# Core.net
KiCad netlist of a schematic drawn in Altium Designer
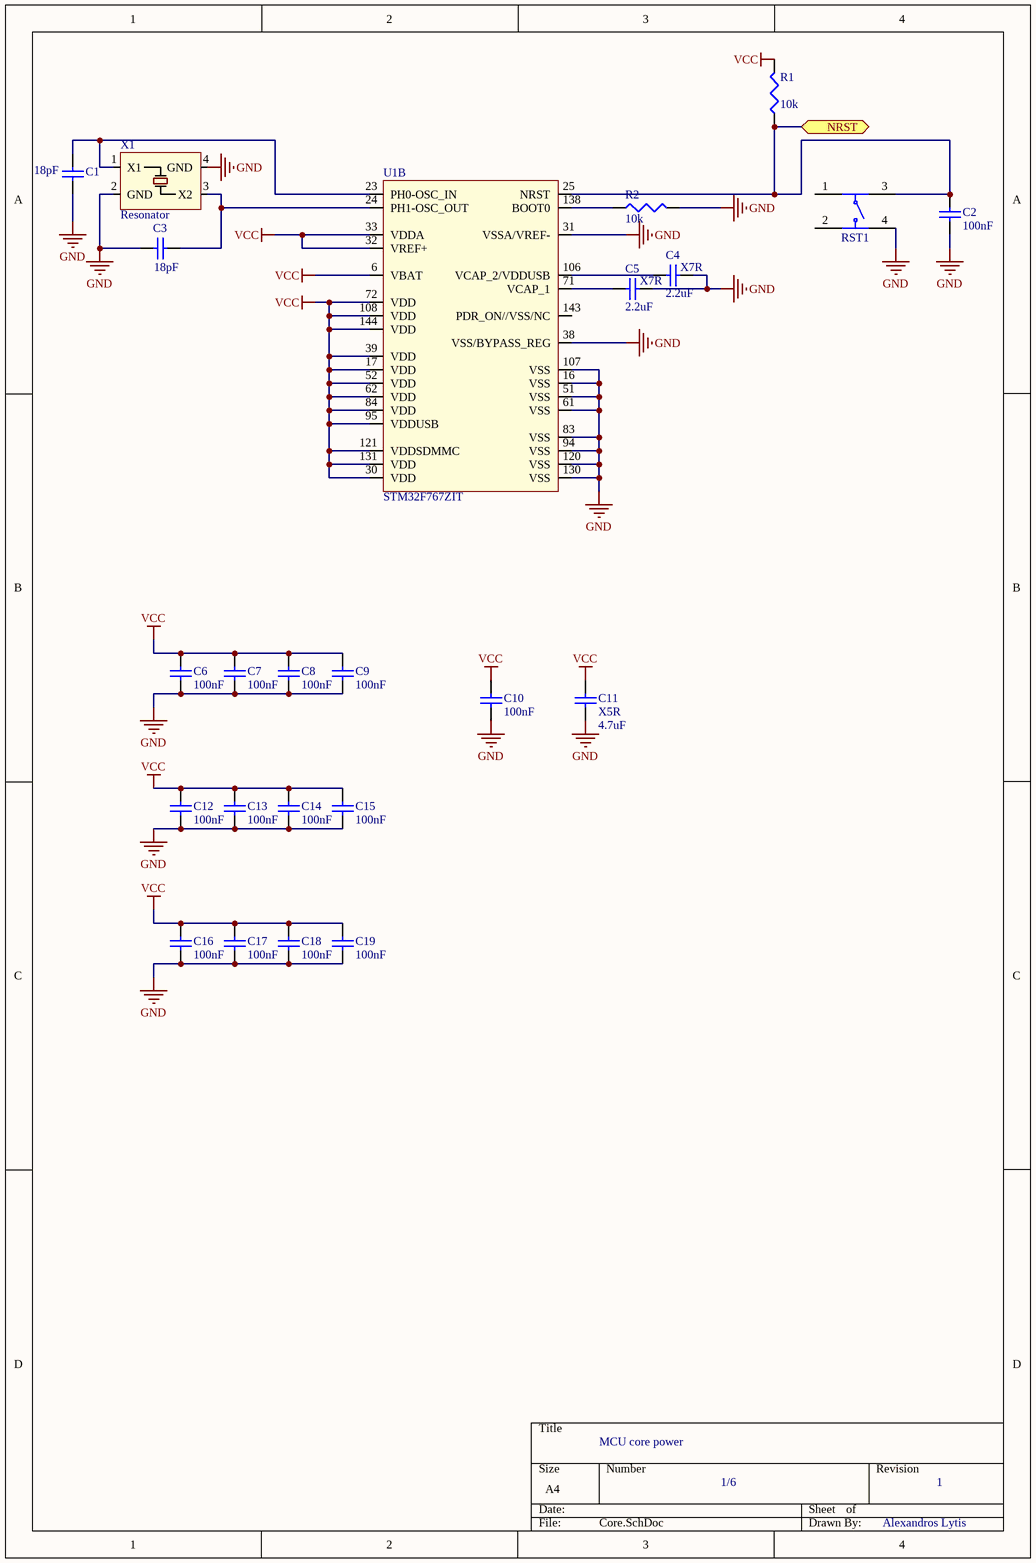
[diagram p0: Core.SchDoc]

(export (version "E")
  (design (tool "Eeschema 10.0.6"))
  (components
    (comp (ref "C1")
      (value "18pF")
      (footprint "CAP0603")
      (description "Capacitor (Semiconductor SIM Model)")
      (fields (field (name "Comment") "Cap Semi") (field (name "PUBLISHER") "Altium Limited"))
      (libsource (lib "Miscellaneous Devices") (part "Cap Semi"))
    )
    (comp (ref "C2")
      (value "100nF")
      (footprint "CAP0603")
      (description "Capacitor (Semiconductor SIM Model)")
      (fields (field (name "Comment") "Cap Semi") (field (name "PUBLISHER") "Altium Limited"))
      (libsource (lib "Miscellaneous Devices") (part "Cap Semi"))
    )
    (comp (ref "C3")
      (value "18pF")
      (footprint "CAP0603")
      (description "Capacitor (Semiconductor SIM Model)")
      (fields (field (name "Comment") "Cap Semi") (field (name "PUBLISHER") "Altium Limited"))
      (libsource (lib "Miscellaneous Devices") (part "Cap Semi"))
    )
    (comp (ref "C4")
      (value "X7R")
      (footprint "CAP0603")
      (description "Capacitor (Semiconductor SIM Model)")
      (fields (field (name "ALTIUM_VALUE") "2.2uF") (field (name "PUBLISHER") "Altium Limited"))
      (libsource (lib "Miscellaneous Devices") (part "Cap Semi"))
    )
    (comp (ref "C5")
      (value "X7R")
      (footprint "CAP0603")
      (description "Capacitor (Semiconductor SIM Model)")
      (fields (field (name "ALTIUM_VALUE") "2.2uF") (field (name "PUBLISHER") "Altium Limited"))
      (libsource (lib "Miscellaneous Devices") (part "Cap Semi"))
    )
    (comp (ref "C6")
      (value "100nF")
      (footprint "CAP0603")
      (description "Capacitor (Semiconductor SIM Model)")
      (fields (field (name "Comment") "Cap Semi") (field (name "PUBLISHER") "Altium Limited"))
      (libsource (lib "Miscellaneous Devices") (part "Cap Semi"))
    )
    (comp (ref "C7")
      (value "100nF")
      (footprint "CAP0603")
      (description "Capacitor (Semiconductor SIM Model)")
      (fields (field (name "Comment") "Cap Semi") (field (name "PUBLISHER") "Altium Limited"))
      (libsource (lib "Miscellaneous Devices") (part "Cap Semi"))
    )
    (comp (ref "C8")
      (value "100nF")
      (footprint "CAP0603")
      (description "Capacitor (Semiconductor SIM Model)")
      (fields (field (name "Comment") "Cap Semi") (field (name "PUBLISHER") "Altium Limited"))
      (libsource (lib "Miscellaneous Devices") (part "Cap Semi"))
    )
    (comp (ref "C9")
      (value "100nF")
      (footprint "CAP0603")
      (description "Capacitor (Semiconductor SIM Model)")
      (fields (field (name "Comment") "Cap Semi") (field (name "PUBLISHER") "Altium Limited"))
      (libsource (lib "Miscellaneous Devices") (part "Cap Semi"))
    )
    (comp (ref "C10")
      (value "100nF")
      (footprint "CAP0603")
      (description "Capacitor (Semiconductor SIM Model)")
      (fields (field (name "Comment") "Cap Semi") (field (name "PUBLISHER") "Altium Limited"))
      (libsource (lib "Miscellaneous Devices") (part "Cap Semi"))
    )
    (comp (ref "C11")
      (value "X5R")
      (footprint "CAP0603")
      (description "Capacitor (Semiconductor SIM Model)")
      (fields (field (name "ALTIUM_VALUE") "4.7uF") (field (name "PUBLISHER") "Altium Limited"))
      (libsource (lib "Miscellaneous Devices") (part "Cap Semi"))
    )
    (comp (ref "C12")
      (value "100nF")
      (footprint "CAP0603")
      (description "Capacitor (Semiconductor SIM Model)")
      (fields (field (name "Comment") "Cap Semi") (field (name "PUBLISHER") "Altium Limited"))
      (libsource (lib "Miscellaneous Devices") (part "Cap Semi"))
    )
    (comp (ref "C13")
      (value "100nF")
      (footprint "CAP0603")
      (description "Capacitor (Semiconductor SIM Model)")
      (fields (field (name "Comment") "Cap Semi") (field (name "PUBLISHER") "Altium Limited"))
      (libsource (lib "Miscellaneous Devices") (part "Cap Semi"))
    )
    (comp (ref "C14")
      (value "100nF")
      (footprint "CAP0603")
      (description "Capacitor (Semiconductor SIM Model)")
      (fields (field (name "Comment") "Cap Semi") (field (name "PUBLISHER") "Altium Limited"))
      (libsource (lib "Miscellaneous Devices") (part "Cap Semi"))
    )
    (comp (ref "C15")
      (value "100nF")
      (footprint "CAP0603")
      (description "Capacitor (Semiconductor SIM Model)")
      (fields (field (name "Comment") "Cap Semi") (field (name "PUBLISHER") "Altium Limited"))
      (libsource (lib "Miscellaneous Devices") (part "Cap Semi"))
    )
    (comp (ref "C16")
      (value "100nF")
      (footprint "CAP0603")
      (description "Capacitor (Semiconductor SIM Model)")
      (fields (field (name "Comment") "Cap Semi") (field (name "PUBLISHER") "Altium Limited"))
      (libsource (lib "Miscellaneous Devices") (part "Cap Semi"))
    )
    (comp (ref "C17")
      (value "100nF")
      (footprint "CAP0603")
      (description "Capacitor (Semiconductor SIM Model)")
      (fields (field (name "Comment") "Cap Semi") (field (name "PUBLISHER") "Altium Limited"))
      (libsource (lib "Miscellaneous Devices") (part "Cap Semi"))
    )
    (comp (ref "C18")
      (value "100nF")
      (footprint "CAP0603")
      (description "Capacitor (Semiconductor SIM Model)")
      (fields (field (name "Comment") "Cap Semi") (field (name "PUBLISHER") "Altium Limited"))
      (libsource (lib "Miscellaneous Devices") (part "Cap Semi"))
    )
    (comp (ref "C19")
      (value "100nF")
      (footprint "CAP0603")
      (description "Capacitor (Semiconductor SIM Model)")
      (fields (field (name "Comment") "Cap Semi") (field (name "PUBLISHER") "Altium Limited"))
      (libsource (lib "Miscellaneous Devices") (part "Cap Semi"))
    )
    (comp (ref "R1")
      (value "10k")
      (footprint "RES0603")
      (description "Resistor")
      (fields (field (name "Comment") "Res3") (field (name "PUBLISHER") "Altium Limited"))
      (libsource (lib "Miscellaneous Devices") (part "Res3"))
    )
    (comp (ref "R2")
      (value "10k")
      (footprint "RES0603")
      (description "Resistor")
      (fields (field (name "Comment") "Res3") (field (name "PUBLISHER") "Altium Limited"))
      (libsource (lib "Miscellaneous Devices") (part "Res3"))
    )
    (comp (ref "RST1")
      (value "430152043826")
      (footprint "4301x20438x6")
      (description "WS-TASV 6x6 mm SMD")
      (fields (field (name "MANUFACTURER") "Wurth Elektronik") (field (name "CREATED BY") "Baojun Chen"))
      (libsource (lib "WS-TASV_rev15a") (part "WS-TASV, 430152043826"))
    )
    (comp (ref "U1")
      (value "STM32F767ZIT")
      (footprint "TSQFP50P2200X2200X160-144N")
      (libsource (lib "Custom_Libraries") (part "STM32F767ZIT"))
    )
    (comp (ref "X1")
      (value "Resonator")
      (footprint "ABM8G")
      (libsource (lib "Custom_Libraries") (part "ABM8G-MHz"))
    )
  )
  (nets
    (net (code "1") (name "/NRST") (class "Default")
      (node (ref "C2") (pin "2") (pinfunction "2_2") (pintype "passive"))
      (node (ref "R1") (pin "1") (pinfunction "1_1") (pintype "passive"))
      (node (ref "RST1") (pin "3") (pinfunction "3_3") (pintype "passive"))
      (node (ref "U1") (pin "25") (pinfunction "NRST_25") (pintype "power_in"))
    )
    (net (code "2") (name "GND") (class "Default")
      (node (ref "C1") (pin "1") (pinfunction "1_1") (pintype "passive"))
      (node (ref "C10") (pin "1") (pinfunction "1_1") (pintype "passive"))
      (node (ref "C11") (pin "1") (pinfunction "1_1") (pintype "passive"))
      (node (ref "C12") (pin "1") (pinfunction "1_1") (pintype "passive"))
      (node (ref "C13") (pin "1") (pinfunction "1_1") (pintype "passive"))
      (node (ref "C14") (pin "1") (pinfunction "1_1") (pintype "passive"))
      (node (ref "C15") (pin "1") (pinfunction "1_1") (pintype "passive"))
      (node (ref "C16") (pin "1") (pinfunction "1_1") (pintype "passive"))
      (node (ref "C17") (pin "1") (pinfunction "1_1") (pintype "passive"))
      (node (ref "C18") (pin "1") (pinfunction "1_1") (pintype "passive"))
      (node (ref "C19") (pin "1") (pinfunction "1_1") (pintype "passive"))
      (node (ref "C2") (pin "1") (pinfunction "1_1") (pintype "passive"))
      (node (ref "C3") (pin "1") (pinfunction "1_1") (pintype "passive"))
      (node (ref "C4") (pin "2") (pinfunction "2_2") (pintype "passive"))
      (node (ref "C5") (pin "2") (pinfunction "2_2") (pintype "passive"))
      (node (ref "C6") (pin "1") (pinfunction "1_1") (pintype "passive"))
      (node (ref "C7") (pin "1") (pinfunction "1_1") (pintype "passive"))
      (node (ref "C8") (pin "1") (pinfunction "1_1") (pintype "passive"))
      (node (ref "C9") (pin "1") (pinfunction "1_1") (pintype "passive"))
      (node (ref "R2") (pin "2") (pinfunction "2_2") (pintype "passive"))
      (node (ref "RST1") (pin "4") (pinfunction "4_4") (pintype "passive"))
      (node (ref "U1") (pin "107") (pinfunction "VSS_107") (pintype "power_in"))
      (node (ref "U1") (pin "120") (pinfunction "VSS_120") (pintype "power_in"))
      (node (ref "U1") (pin "130") (pinfunction "VSS_130") (pintype "power_in"))
      (node (ref "U1") (pin "16") (pinfunction "VSS_16") (pintype "power_in"))
      (node (ref "U1") (pin "31") (pinfunction "VSSA/VREF-_31") (pintype "power_in"))
      (node (ref "U1") (pin "38") (pinfunction "VSS/BYPASS_REG_38") (pintype "power_in"))
      (node (ref "U1") (pin "51") (pinfunction "VSS_51") (pintype "power_in"))
      (node (ref "U1") (pin "61") (pinfunction "VSS_61") (pintype "power_in"))
      (node (ref "U1") (pin "83") (pinfunction "VSS_83") (pintype "power_in"))
      (node (ref "U1") (pin "94") (pinfunction "VSS_94") (pintype "power_in"))
      (node (ref "X1") (pin "2") (pinfunction "GND_2") (pintype "passive"))
      (node (ref "X1") (pin "4") (pinfunction "GND_4") (pintype "passive"))
    )
    (net (code "3") (name "Net-(U1B-BOOT0)") (class "Default")
      (node (ref "R2") (pin "1") (pinfunction "1_1") (pintype "passive"))
      (node (ref "U1") (pin "138") (pinfunction "BOOT0_138") (pintype "power_in"))
    )
    (net (code "4") (name "Net-(U1B-PH0-OSC_IN)") (class "Default")
      (node (ref "C1") (pin "2") (pinfunction "2_2") (pintype "passive"))
      (node (ref "U1") (pin "23") (pinfunction "PH0-OSC_IN_23") (pintype "power_in"))
      (node (ref "X1") (pin "1") (pinfunction "X1_1") (pintype "passive"))
    )
    (net (code "5") (name "Net-(U1B-PH1-OSC_OUT)") (class "Default")
      (node (ref "C3") (pin "2") (pinfunction "2_2") (pintype "passive"))
      (node (ref "U1") (pin "24") (pinfunction "PH1-OSC_OUT_24") (pintype "power_in"))
      (node (ref "X1") (pin "3") (pinfunction "X2_3") (pintype "passive"))
    )
    (net (code "6") (name "Net-(U1B-VCAP_1)") (class "Default")
      (node (ref "C5") (pin "1") (pinfunction "1_1") (pintype "passive"))
      (node (ref "U1") (pin "71") (pinfunction "VCAP_1_71") (pintype "power_in"))
    )
    (net (code "7") (name "Net-(U1B-VCAP_2{slash}VDDUSB)") (class "Default")
      (node (ref "C4") (pin "1") (pinfunction "1_1") (pintype "passive"))
      (node (ref "U1") (pin "106") (pinfunction "VCAP_2/VDDUSB_106") (pintype "power_in"))
    )
    (net (code "8") (name "VCC") (class "Default")
      (node (ref "C10") (pin "2") (pinfunction "2_2") (pintype "passive"))
      (node (ref "C11") (pin "2") (pinfunction "2_2") (pintype "passive"))
      (node (ref "C12") (pin "2") (pinfunction "2_2") (pintype "passive"))
      (node (ref "C13") (pin "2") (pinfunction "2_2") (pintype "passive"))
      (node (ref "C14") (pin "2") (pinfunction "2_2") (pintype "passive"))
      (node (ref "C15") (pin "2") (pinfunction "2_2") (pintype "passive"))
      (node (ref "C16") (pin "2") (pinfunction "2_2") (pintype "passive"))
      (node (ref "C17") (pin "2") (pinfunction "2_2") (pintype "passive"))
      (node (ref "C18") (pin "2") (pinfunction "2_2") (pintype "passive"))
      (node (ref "C19") (pin "2") (pinfunction "2_2") (pintype "passive"))
      (node (ref "C6") (pin "2") (pinfunction "2_2") (pintype "passive"))
      (node (ref "C7") (pin "2") (pinfunction "2_2") (pintype "passive"))
      (node (ref "C8") (pin "2") (pinfunction "2_2") (pintype "passive"))
      (node (ref "C9") (pin "2") (pinfunction "2_2") (pintype "passive"))
      (node (ref "R1") (pin "2") (pinfunction "2_2") (pintype "passive"))
      (node (ref "U1") (pin "108") (pinfunction "VDD_108") (pintype "power_in"))
      (node (ref "U1") (pin "121") (pinfunction "VDDSDMMC_121") (pintype "power_in"))
      (node (ref "U1") (pin "131") (pinfunction "VDD_131") (pintype "power_in"))
      (node (ref "U1") (pin "144") (pinfunction "VDD_144") (pintype "power_in"))
      (node (ref "U1") (pin "17") (pinfunction "VDD_17") (pintype "power_in"))
      (node (ref "U1") (pin "30") (pinfunction "VDD_30") (pintype "power_in"))
      (node (ref "U1") (pin "32") (pinfunction "VREF+_32") (pintype "power_in"))
      (node (ref "U1") (pin "33") (pinfunction "VDDA_33") (pintype "power_in"))
      (node (ref "U1") (pin "39") (pinfunction "VDD_39") (pintype "power_in"))
      (node (ref "U1") (pin "52") (pinfunction "VDD_52") (pintype "power_in"))
      (node (ref "U1") (pin "6") (pinfunction "VBAT_6") (pintype "power_in"))
      (node (ref "U1") (pin "62") (pinfunction "VDD_62") (pintype "power_in"))
      (node (ref "U1") (pin "72") (pinfunction "VDD_72") (pintype "power_in"))
      (node (ref "U1") (pin "84") (pinfunction "VDD_84") (pintype "power_in"))
      (node (ref "U1") (pin "95") (pinfunction "VDDUSB_95") (pintype "power_in"))
    )
    (net (code "9") (name "unconnected-(RST1-Pad1)") (class "Default")
      (node (ref "RST1") (pin "1") (pinfunction "1_1") (pintype "passive"))
    )
    (net (code "10") (name "unconnected-(RST1-Pad2)") (class "Default")
      (node (ref "RST1") (pin "2") (pinfunction "2_2") (pintype "passive"))
    )
    (net (code "11") (name "unconnected-(U1B-PDR_ON{slash}{slash}VSS{slash}NC-Pad143)") (class "Default")
      (node (ref "U1") (pin "143") (pinfunction "PDR_ON//VSS/NC_143") (pintype "power_in"))
    )
  )
)
